# generator.net
KiCad netlist of a schematic drawn in EAGLE
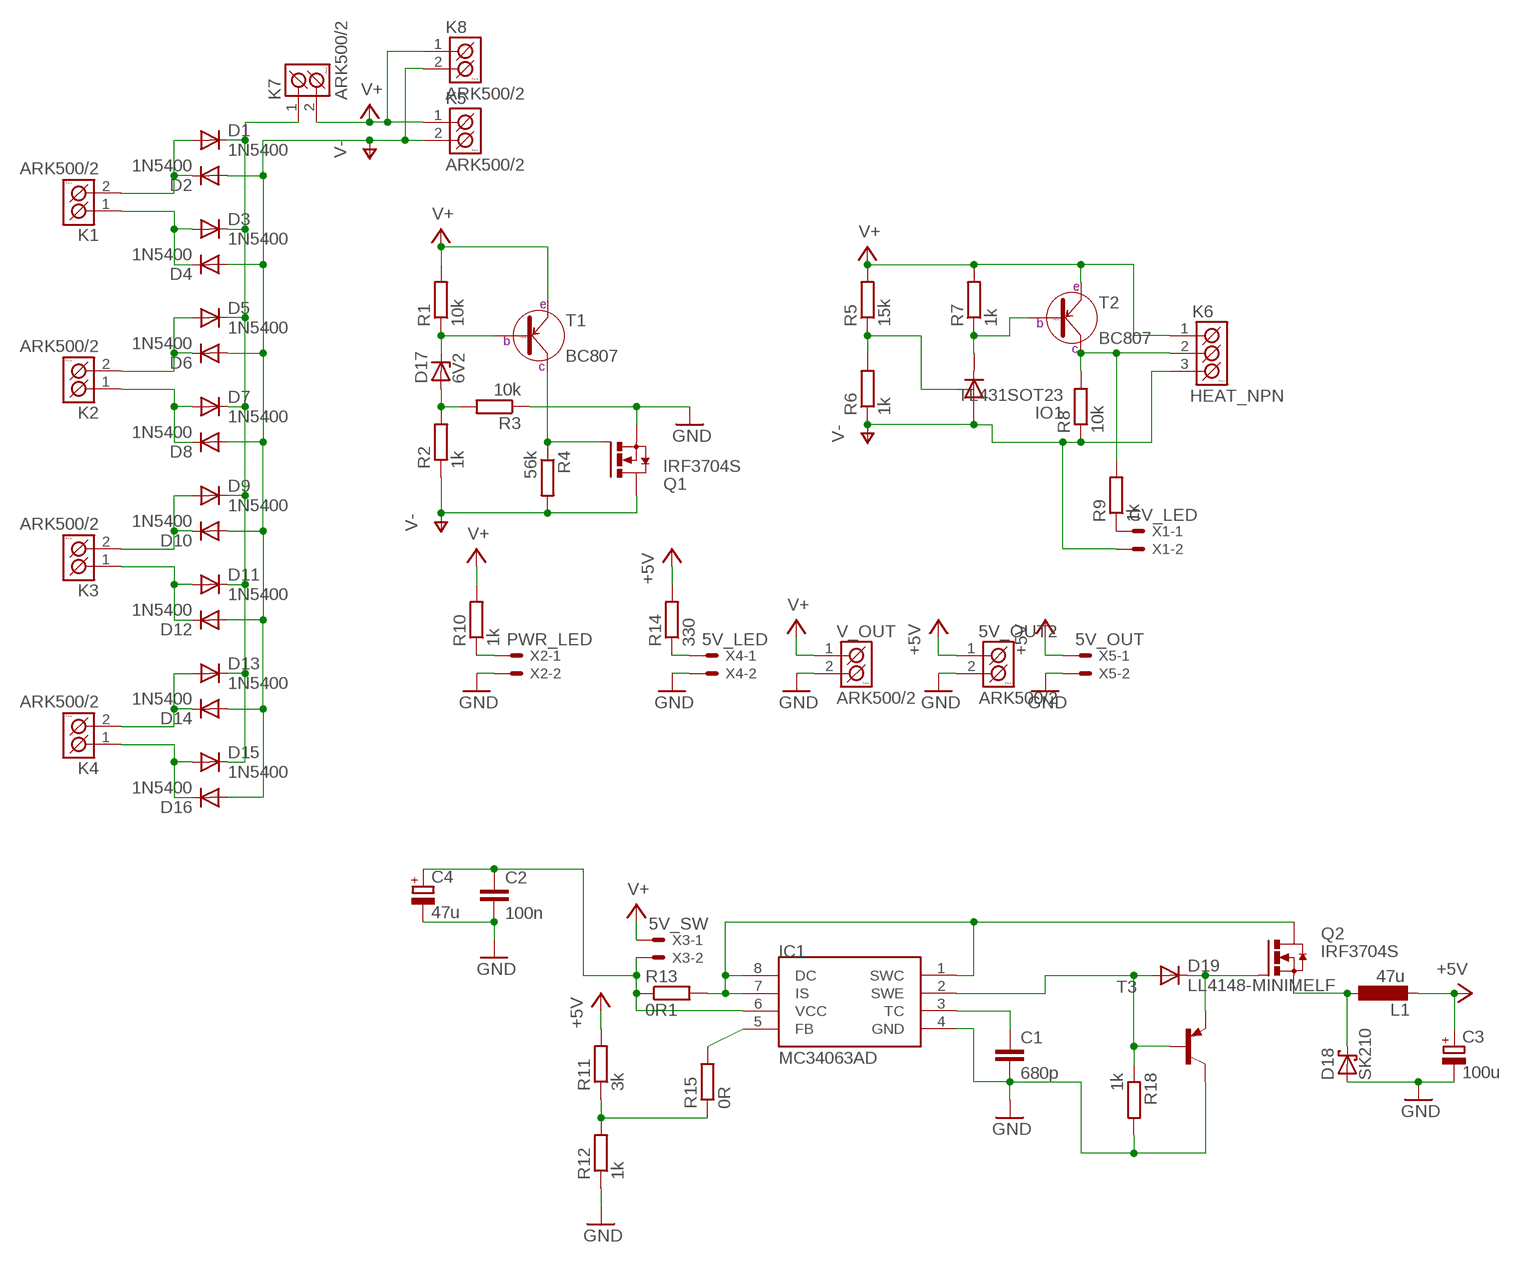
[diagram p0: schematic, sheet 1]

(export (version "E")
  (design (tool "Eeschema 10.0.6"))
  (components
    (comp (ref "5V_OUT2")
      (value "ARK500/2")
      (footprint "eagle-import:ARK500_2")
      (libsource (lib "eagle-import") (part "ARK500/2"))
    )
    (comp (ref "C1")
      (value "680p")
      (footprint "eagle-import:C0805")
      (libsource (lib "eagle-import") (part "C-EUC0805"))
    )
    (comp (ref "C2")
      (value "100n")
      (footprint "eagle-import:C0805")
      (libsource (lib "eagle-import") (part "C-EUC0805"))
    )
    (comp (ref "C3")
      (value "100u")
      (footprint "eagle-import:PANASONIC_D")
      (libsource (lib "eagle-import") (part "CPOL-EUD"))
    )
    (comp (ref "C4")
      (value "47u")
      (footprint "eagle-import:PANASONIC_D")
      (libsource (lib "eagle-import") (part "CPOL-EUD"))
    )
    (comp (ref "D1")
      (value "1N5400")
      (footprint "eagle-import:DO201-15")
      (libsource (lib "eagle-import") (part "1N5400"))
    )
    (comp (ref "D2")
      (value "1N5400")
      (footprint "eagle-import:DO201-15")
      (libsource (lib "eagle-import") (part "1N5400"))
    )
    (comp (ref "D3")
      (value "1N5400")
      (footprint "eagle-import:DO201-15")
      (libsource (lib "eagle-import") (part "1N5400"))
    )
    (comp (ref "D4")
      (value "1N5400")
      (footprint "eagle-import:DO201-15")
      (libsource (lib "eagle-import") (part "1N5400"))
    )
    (comp (ref "D5")
      (value "1N5400")
      (footprint "eagle-import:DO201-15")
      (libsource (lib "eagle-import") (part "1N5400"))
    )
    (comp (ref "D6")
      (value "1N5400")
      (footprint "eagle-import:DO201-15")
      (libsource (lib "eagle-import") (part "1N5400"))
    )
    (comp (ref "D7")
      (value "1N5400")
      (footprint "eagle-import:DO201-15")
      (libsource (lib "eagle-import") (part "1N5400"))
    )
    (comp (ref "D8")
      (value "1N5400")
      (footprint "eagle-import:DO201-15")
      (libsource (lib "eagle-import") (part "1N5400"))
    )
    (comp (ref "D9")
      (value "1N5400")
      (footprint "eagle-import:DO201-15")
      (libsource (lib "eagle-import") (part "1N5400"))
    )
    (comp (ref "D10")
      (value "1N5400")
      (footprint "eagle-import:DO201-15")
      (libsource (lib "eagle-import") (part "1N5400"))
    )
    (comp (ref "D11")
      (value "1N5400")
      (footprint "eagle-import:DO201-15")
      (libsource (lib "eagle-import") (part "1N5400"))
    )
    (comp (ref "D12")
      (value "1N5400")
      (footprint "eagle-import:DO201-15")
      (libsource (lib "eagle-import") (part "1N5400"))
    )
    (comp (ref "D13")
      (value "1N5400")
      (footprint "eagle-import:DO201-15")
      (libsource (lib "eagle-import") (part "1N5400"))
    )
    (comp (ref "D14")
      (value "1N5400")
      (footprint "eagle-import:DO201-15")
      (libsource (lib "eagle-import") (part "1N5400"))
    )
    (comp (ref "D15")
      (value "1N5400")
      (footprint "eagle-import:DO201-15")
      (libsource (lib "eagle-import") (part "1N5400"))
    )
    (comp (ref "D16")
      (value "1N5400")
      (footprint "eagle-import:DO201-15")
      (libsource (lib "eagle-import") (part "1N5400"))
    )
    (comp (ref "D17")
      (value "6V2")
      (footprint "eagle-import:SOD80C")
      (libsource (lib "eagle-import") (part "ZENER-DIODESOD80C"))
    )
    (comp (ref "D18")
      (value "SK210")
      (footprint "eagle-import:SMB")
      (libsource (lib "eagle-import") (part "SCHOTTKY-DIODESMD"))
    )
    (comp (ref "D19")
      (value "LL4148-MINIMELF")
      (footprint "eagle-import:SOD80C")
      (libsource (lib "eagle-import") (part "PMLL41SOD80C"))
    )
    (comp (ref "IC1")
      (value "MC34063AD")
      (footprint "eagle-import:SOIC8")
      (libsource (lib "eagle-import") (part "MC34063AD"))
    )
    (comp (ref "IO1")
      (value "TL431SOT23")
      (footprint "eagle-import:SOT23")
      (fields (field (name "MPN") "TL431BFDT"))
      (libsource (lib "eagle-import") (part "TL431SOT23"))
    )
    (comp (ref "K1")
      (value "ARK500/2")
      (footprint "eagle-import:ARK500_2")
      (libsource (lib "eagle-import") (part "ARK500/2"))
    )
    (comp (ref "K2")
      (value "ARK500/2")
      (footprint "eagle-import:ARK500_2")
      (libsource (lib "eagle-import") (part "ARK500/2"))
    )
    (comp (ref "K3")
      (value "ARK500/2")
      (footprint "eagle-import:ARK500_2")
      (libsource (lib "eagle-import") (part "ARK500/2"))
    )
    (comp (ref "K4")
      (value "ARK500/2")
      (footprint "eagle-import:ARK500_2")
      (libsource (lib "eagle-import") (part "ARK500/2"))
    )
    (comp (ref "K5")
      (value "ARK500/2")
      (footprint "eagle-import:ARK500_2")
      (libsource (lib "eagle-import") (part "ARK500/2"))
    )
    (comp (ref "K6")
      (value "HEAT_NPN")
      (footprint "eagle-import:ARK500_3")
      (libsource (lib "eagle-import") (part "ARK500/3"))
    )
    (comp (ref "K7")
      (value "ARK500/2")
      (footprint "eagle-import:ARK500_2")
      (libsource (lib "eagle-import") (part "ARK500/2"))
    )
    (comp (ref "K8")
      (value "ARK500/2")
      (footprint "eagle-import:ARK500_2")
      (libsource (lib "eagle-import") (part "ARK500/2"))
    )
    (comp (ref "L1")
      (value "47u")
      (footprint "eagle-import:TJ3-U1")
      (libsource (lib "eagle-import") (part "L-EUTJ3-U1"))
    )
    (comp (ref "Q1")
      (value "IRF3704S")
      (footprint "eagle-import:D2PACK")
      (libsource (lib "eagle-import") (part "IRF3704S"))
    )
    (comp (ref "Q2")
      (value "IRF3704S")
      (footprint "eagle-import:D2PACK")
      (libsource (lib "eagle-import") (part "IRF3704S"))
    )
    (comp (ref "R1")
      (value "10k")
      (footprint "eagle-import:R0805")
      (libsource (lib "eagle-import") (part "R-EU_R0805"))
    )
    (comp (ref "R2")
      (value "1k")
      (footprint "eagle-import:R0805")
      (libsource (lib "eagle-import") (part "R-EU_R0805"))
    )
    (comp (ref "R3")
      (value "10k")
      (footprint "eagle-import:R0805")
      (libsource (lib "eagle-import") (part "R-EU_R0805"))
    )
    (comp (ref "R4")
      (value "56k")
      (footprint "eagle-import:R0805")
      (libsource (lib "eagle-import") (part "R-EU_R0805"))
    )
    (comp (ref "R5")
      (value "15k")
      (footprint "eagle-import:R0805")
      (libsource (lib "eagle-import") (part "R-EU_R0805"))
    )
    (comp (ref "R6")
      (value "1k")
      (footprint "eagle-import:R0805")
      (libsource (lib "eagle-import") (part "R-EU_R0805"))
    )
    (comp (ref "R7")
      (value "1k")
      (footprint "eagle-import:R0805")
      (libsource (lib "eagle-import") (part "R-EU_R0805"))
    )
    (comp (ref "R8")
      (value "10k")
      (footprint "eagle-import:R0805")
      (libsource (lib "eagle-import") (part "R-EU_R0805"))
    )
    (comp (ref "R9")
      (value "1k")
      (footprint "eagle-import:R0805")
      (libsource (lib "eagle-import") (part "R-EU_R0805"))
    )
    (comp (ref "R10")
      (value "1k")
      (footprint "eagle-import:R0805")
      (libsource (lib "eagle-import") (part "R-EU_R0805"))
    )
    (comp (ref "R11")
      (value "3k")
      (footprint "eagle-import:R0805")
      (libsource (lib "eagle-import") (part "R-EU_R0805"))
    )
    (comp (ref "R12")
      (value "1k")
      (footprint "eagle-import:R0805")
      (libsource (lib "eagle-import") (part "R-EU_R0805"))
    )
    (comp (ref "R13")
      (value "0R1")
      (footprint "eagle-import:R0805")
      (libsource (lib "eagle-import") (part "R-EU_R0805"))
    )
    (comp (ref "R14")
      (value "330")
      (footprint "eagle-import:R0805")
      (libsource (lib "eagle-import") (part "R-EU_R0805"))
    )
    (comp (ref "R15")
      (value "0R")
      (footprint "eagle-import:R1206")
      (libsource (lib "eagle-import") (part "R-EU_R1206"))
    )
    (comp (ref "R18")
      (value "1k")
      (footprint "eagle-import:R0805")
      (libsource (lib "eagle-import") (part "resistor_R-EU_R0805"))
    )
    (comp (ref "T1")
      (value "BC807")
      (footprint "eagle-import:SOT-23")
      (libsource (lib "eagle-import") (part "BC807"))
    )
    (comp (ref "T2")
      (value "BC807")
      (footprint "eagle-import:SOT-23")
      (libsource (lib "eagle-import") (part "BC807"))
    )
    (comp (ref "T3")
      (value "BC807-16-PNP-SOT23-BEC")
      (footprint "eagle-import:SOT23-BEC")
      (libsource (lib "eagle-import") (part "-PNP-SOT23-BECBC807-16"))
    )
    (comp (ref "V_OUT")
      (value "ARK500/2")
      (footprint "eagle-import:ARK500_2")
      (libsource (lib "eagle-import") (part "ARK500/2"))
    )
    (comp (ref "X1")
      (value "CV_LED")
      (footprint "eagle-import:22-23-2021")
      (fields (field (name "MF") "MOLEX") (field (name "MPN") "22-23-2021"))
      (libsource (lib "eagle-import") (part "22-23-2021"))
    )
    (comp (ref "X2")
      (value "PWR_LED")
      (footprint "eagle-import:22-23-2021")
      (fields (field (name "MF") "MOLEX") (field (name "MPN") "22-23-2021"))
      (libsource (lib "eagle-import") (part "22-23-2021"))
    )
    (comp (ref "X3")
      (value "5V_SW")
      (footprint "eagle-import:22-23-2021")
      (fields (field (name "MF") "MOLEX") (field (name "MPN") "22-23-2021"))
      (libsource (lib "eagle-import") (part "22-23-2021"))
    )
    (comp (ref "X4")
      (value "5V_LED")
      (footprint "eagle-import:22-23-2021")
      (fields (field (name "MF") "MOLEX") (field (name "MPN") "22-23-2021"))
      (libsource (lib "eagle-import") (part "22-23-2021"))
    )
    (comp (ref "X5")
      (value "5V_OUT")
      (footprint "eagle-import:22-23-2021")
      (fields (field (name "MF") "MOLEX") (field (name "MPN") "22-23-2021"))
      (libsource (lib "eagle-import") (part "22-23-2021"))
    )
  )
  (nets
    (net (code "1") (name "+5V") (class "Default")
      (node (ref "5V_OUT2") (pin "1") (pinfunction "K1_1") (pintype "passive"))
      (node (ref "C3") (pin "+") (pinfunction "+_+") (pintype "passive"))
      (node (ref "L1") (pin "2") (pinfunction "2_2") (pintype "passive"))
      (node (ref "R11") (pin "2") (pinfunction "2_2") (pintype "passive"))
      (node (ref "R14") (pin "2") (pinfunction "2_2") (pintype "passive"))
      (node (ref "X5") (pin "1") (pinfunction "S_1") (pintype "passive"))
    )
    (net (code "2") (name "GND") (class "Default")
      (node (ref "5V_OUT2") (pin "2") (pinfunction "K2_2") (pintype "passive"))
      (node (ref "C1") (pin "2") (pinfunction "2_2") (pintype "passive"))
      (node (ref "C2") (pin "2") (pinfunction "2_2") (pintype "passive"))
      (node (ref "C3") (pin "-") (pinfunction "-_-") (pintype "passive"))
      (node (ref "C4") (pin "-") (pinfunction "-_-") (pintype "passive"))
      (node (ref "D18") (pin "A") (pinfunction "A_A") (pintype "passive"))
      (node (ref "IC1") (pin "4") (pinfunction "GND_4") (pintype "passive"))
      (node (ref "Q1") (pin "3") (pinfunction "S_3") (pintype "passive"))
      (node (ref "R12") (pin "1") (pinfunction "1_1") (pintype "passive"))
      (node (ref "R18") (pin "2") (pinfunction "2_2") (pintype "passive"))
      (node (ref "R3") (pin "1") (pinfunction "1_1") (pintype "passive"))
      (node (ref "T3") (pin "C") (pinfunction "C_C") (pintype "passive"))
      (node (ref "V_OUT") (pin "2") (pinfunction "K2_2") (pintype "passive"))
      (node (ref "X2") (pin "2") (pinfunction "S_2") (pintype "passive"))
      (node (ref "X4") (pin "2") (pinfunction "S_2") (pintype "passive"))
      (node (ref "X5") (pin "2") (pinfunction "S_2") (pintype "passive"))
    )
    (net (code "3") (name "Net-(D17-PadA)") (class "Default")
      (node (ref "D17") (pin "A") (pinfunction "A_A") (pintype "passive"))
      (node (ref "R2") (pin "2") (pinfunction "2_2") (pintype "passive"))
      (node (ref "R3") (pin "2") (pinfunction "2_2") (pintype "passive"))
    )
    (net (code "4") (name "Net-(IC1-DC)") (class "Default")
      (node (ref "IC1") (pin "1") (pinfunction "SWC_1") (pintype "passive"))
      (node (ref "IC1") (pin "7") (pinfunction "IS_7") (pintype "passive"))
      (node (ref "IC1") (pin "8") (pinfunction "DC_8") (pintype "passive"))
      (node (ref "Q2") (pin "2") (pinfunction "D_2") (pintype "passive"))
      (node (ref "R13") (pin "2") (pinfunction "2_2") (pintype "passive"))
    )
    (net (code "5") (name "Net-(IC1-FB)") (class "Default")
      (node (ref "IC1") (pin "5") (pinfunction "FB_5") (pintype "passive"))
      (node (ref "R15") (pin "2") (pinfunction "2_2") (pintype "passive"))
    )
    (net (code "6") (name "Net-(IC1-SWE)") (class "Default")
      (node (ref "D19") (pin "A") (pinfunction "A_A") (pintype "passive"))
      (node (ref "IC1") (pin "2") (pinfunction "SWE_2") (pintype "passive"))
      (node (ref "R18") (pin "1") (pinfunction "1_1") (pintype "passive"))
      (node (ref "T3") (pin "B") (pinfunction "B_B") (pintype "passive"))
    )
    (net (code "7") (name "Net-(IC1-TC)") (class "Default")
      (node (ref "C1") (pin "1") (pinfunction "1_1") (pintype "passive"))
      (node (ref "IC1") (pin "3") (pinfunction "TC_3") (pintype "passive"))
    )
    (net (code "8") (name "Net-(IC1-VCC)") (class "Default")
      (node (ref "C2") (pin "1") (pinfunction "1_1") (pintype "passive"))
      (node (ref "C4") (pin "+") (pinfunction "+_+") (pintype "passive"))
      (node (ref "IC1") (pin "6") (pinfunction "VCC_6") (pintype "passive"))
      (node (ref "R13") (pin "1") (pinfunction "1_1") (pintype "passive"))
      (node (ref "X3") (pin "2") (pinfunction "S_2") (pintype "passive"))
    )
    (net (code "9") (name "Net-(IO1-C)") (class "Default")
      (node (ref "IO1") (pin "1") (pinfunction "C_1") (pintype "bidirectional"))
      (node (ref "R7") (pin "1") (pinfunction "1_1") (pintype "passive"))
      (node (ref "T2") (pin "1") (pinfunction "B_1") (pintype "passive"))
    )
    (net (code "10") (name "Net-(IO1-R)") (class "Default")
      (node (ref "IO1") (pin "2") (pinfunction "R_2") (pintype "bidirectional"))
      (node (ref "R5") (pin "1") (pinfunction "1_1") (pintype "passive"))
      (node (ref "R6") (pin "2") (pinfunction "2_2") (pintype "passive"))
    )
    (net (code "11") (name "Net-(K1-K1)") (class "Default")
      (node (ref "D3") (pin "A") (pinfunction "A_A") (pintype "passive"))
      (node (ref "D4") (pin "C") (pinfunction "C_C") (pintype "passive"))
      (node (ref "K1") (pin "1") (pinfunction "K1_1") (pintype "passive"))
    )
    (net (code "12") (name "Net-(K1-K2)") (class "Default")
      (node (ref "D1") (pin "A") (pinfunction "A_A") (pintype "passive"))
      (node (ref "D2") (pin "C") (pinfunction "C_C") (pintype "passive"))
      (node (ref "K1") (pin "2") (pinfunction "K2_2") (pintype "passive"))
    )
    (net (code "13") (name "Net-(K2-K1)") (class "Default")
      (node (ref "D7") (pin "A") (pinfunction "A_A") (pintype "passive"))
      (node (ref "D8") (pin "C") (pinfunction "C_C") (pintype "passive"))
      (node (ref "K2") (pin "1") (pinfunction "K1_1") (pintype "passive"))
    )
    (net (code "14") (name "Net-(K2-K2)") (class "Default")
      (node (ref "D5") (pin "A") (pinfunction "A_A") (pintype "passive"))
      (node (ref "D6") (pin "C") (pinfunction "C_C") (pintype "passive"))
      (node (ref "K2") (pin "2") (pinfunction "K2_2") (pintype "passive"))
    )
    (net (code "15") (name "Net-(K3-K1)") (class "Default")
      (node (ref "D11") (pin "A") (pinfunction "A_A") (pintype "passive"))
      (node (ref "D12") (pin "C") (pinfunction "C_C") (pintype "passive"))
      (node (ref "K3") (pin "1") (pinfunction "K1_1") (pintype "passive"))
    )
    (net (code "16") (name "Net-(K3-K2)") (class "Default")
      (node (ref "D10") (pin "C") (pinfunction "C_C") (pintype "passive"))
      (node (ref "D9") (pin "A") (pinfunction "A_A") (pintype "passive"))
      (node (ref "K3") (pin "2") (pinfunction "K2_2") (pintype "passive"))
    )
    (net (code "17") (name "Net-(K4-K1)") (class "Default")
      (node (ref "D15") (pin "A") (pinfunction "A_A") (pintype "passive"))
      (node (ref "D16") (pin "C") (pinfunction "C_C") (pintype "passive"))
      (node (ref "K4") (pin "1") (pinfunction "K1_1") (pintype "passive"))
    )
    (net (code "18") (name "Net-(K4-K2)") (class "Default")
      (node (ref "D13") (pin "A") (pinfunction "A_A") (pintype "passive"))
      (node (ref "D14") (pin "C") (pinfunction "C_C") (pintype "passive"))
      (node (ref "K4") (pin "2") (pinfunction "K2_2") (pintype "passive"))
    )
    (net (code "19") (name "Net-(K6-K2)") (class "Default")
      (node (ref "K6") (pin "2") (pinfunction "K2_2") (pintype "passive"))
      (node (ref "R8") (pin "2") (pinfunction "2_2") (pintype "passive"))
      (node (ref "R9") (pin "2") (pinfunction "2_2") (pintype "passive"))
      (node (ref "T2") (pin "3") (pinfunction "C_3") (pintype "passive"))
    )
    (net (code "20") (name "Net-(K7-K1)") (class "Default")
      (node (ref "D1") (pin "C") (pinfunction "C_C") (pintype "passive"))
      (node (ref "D11") (pin "C") (pinfunction "C_C") (pintype "passive"))
      (node (ref "D13") (pin "C") (pinfunction "C_C") (pintype "passive"))
      (node (ref "D15") (pin "C") (pinfunction "C_C") (pintype "passive"))
      (node (ref "D3") (pin "C") (pinfunction "C_C") (pintype "passive"))
      (node (ref "D5") (pin "C") (pinfunction "C_C") (pintype "passive"))
      (node (ref "D7") (pin "C") (pinfunction "C_C") (pintype "passive"))
      (node (ref "D9") (pin "C") (pinfunction "C_C") (pintype "passive"))
      (node (ref "K7") (pin "1") (pinfunction "K1_1") (pintype "passive"))
    )
    (net (code "21") (name "Net-(Q1-G)") (class "Default")
      (node (ref "Q1") (pin "1") (pinfunction "G_1") (pintype "passive"))
      (node (ref "R4") (pin "1") (pinfunction "1_1") (pintype "passive"))
      (node (ref "T1") (pin "3") (pinfunction "C_3") (pintype "passive"))
    )
    (net (code "22") (name "Net-(Q2-G)") (class "Default")
      (node (ref "D19") (pin "C") (pinfunction "C_C") (pintype "passive"))
      (node (ref "Q2") (pin "1") (pinfunction "G_1") (pintype "passive"))
      (node (ref "T3") (pin "E") (pinfunction "E_E") (pintype "passive"))
    )
    (net (code "23") (name "Net-(Q2-S)") (class "Default")
      (node (ref "D18") (pin "C") (pinfunction "C_C") (pintype "passive"))
      (node (ref "L1") (pin "1") (pinfunction "1_1") (pintype "passive"))
      (node (ref "Q2") (pin "3") (pinfunction "S_3") (pintype "passive"))
    )
    (net (code "24") (name "Net-(R11-Pad1)") (class "Default")
      (node (ref "R11") (pin "1") (pinfunction "1_1") (pintype "passive"))
      (node (ref "R12") (pin "2") (pinfunction "2_2") (pintype "passive"))
      (node (ref "R15") (pin "1") (pinfunction "1_1") (pintype "passive"))
    )
    (net (code "25") (name "Net-(T1-B)") (class "Default")
      (node (ref "D17") (pin "C") (pinfunction "C_C") (pintype "passive"))
      (node (ref "R1") (pin "1") (pinfunction "1_1") (pintype "passive"))
      (node (ref "T1") (pin "1") (pinfunction "B_1") (pintype "passive"))
    )
    (net (code "26") (name "Net-(X1A-S)") (class "Default")
      (node (ref "R9") (pin "1") (pinfunction "1_1") (pintype "passive"))
      (node (ref "X1") (pin "1") (pinfunction "S_1") (pintype "passive"))
    )
    (net (code "27") (name "Net-(X2A-S)") (class "Default")
      (node (ref "R10") (pin "1") (pinfunction "1_1") (pintype "passive"))
      (node (ref "X2") (pin "1") (pinfunction "S_1") (pintype "passive"))
    )
    (net (code "28") (name "Net-(X4A-S)") (class "Default")
      (node (ref "R14") (pin "1") (pinfunction "1_1") (pintype "passive"))
      (node (ref "X4") (pin "1") (pinfunction "S_1") (pintype "passive"))
    )
    (net (code "29") (name "V+") (class "Default")
      (node (ref "K5") (pin "1") (pinfunction "K1_1") (pintype "passive"))
      (node (ref "K6") (pin "1") (pinfunction "K1_1") (pintype "passive"))
      (node (ref "K7") (pin "2") (pinfunction "K2_2") (pintype "passive"))
      (node (ref "K8") (pin "1") (pinfunction "K1_1") (pintype "passive"))
      (node (ref "R1") (pin "2") (pinfunction "2_2") (pintype "passive"))
      (node (ref "R10") (pin "2") (pinfunction "2_2") (pintype "passive"))
      (node (ref "R5") (pin "2") (pinfunction "2_2") (pintype "passive"))
      (node (ref "R7") (pin "2") (pinfunction "2_2") (pintype "passive"))
      (node (ref "T1") (pin "2") (pinfunction "E_2") (pintype "passive"))
      (node (ref "T2") (pin "2") (pinfunction "E_2") (pintype "passive"))
      (node (ref "V_OUT") (pin "1") (pinfunction "K1_1") (pintype "passive"))
      (node (ref "X3") (pin "1") (pinfunction "S_1") (pintype "passive"))
    )
    (net (code "30") (name "V-") (class "Default")
      (node (ref "D10") (pin "A") (pinfunction "A_A") (pintype "passive"))
      (node (ref "D12") (pin "A") (pinfunction "A_A") (pintype "passive"))
      (node (ref "D14") (pin "A") (pinfunction "A_A") (pintype "passive"))
      (node (ref "D16") (pin "A") (pinfunction "A_A") (pintype "passive"))
      (node (ref "D2") (pin "A") (pinfunction "A_A") (pintype "passive"))
      (node (ref "D4") (pin "A") (pinfunction "A_A") (pintype "passive"))
      (node (ref "D6") (pin "A") (pinfunction "A_A") (pintype "passive"))
      (node (ref "D8") (pin "A") (pinfunction "A_A") (pintype "passive"))
      (node (ref "IO1") (pin "3") (pinfunction "A_3") (pintype "bidirectional"))
      (node (ref "K5") (pin "2") (pinfunction "K2_2") (pintype "passive"))
      (node (ref "K6") (pin "3") (pinfunction "K3_3") (pintype "passive"))
      (node (ref "K8") (pin "2") (pinfunction "K2_2") (pintype "passive"))
      (node (ref "Q1") (pin "2") (pinfunction "D_2") (pintype "passive"))
      (node (ref "R2") (pin "1") (pinfunction "1_1") (pintype "passive"))
      (node (ref "R4") (pin "2") (pinfunction "2_2") (pintype "passive"))
      (node (ref "R6") (pin "1") (pinfunction "1_1") (pintype "passive"))
      (node (ref "R8") (pin "1") (pinfunction "1_1") (pintype "passive"))
      (node (ref "X1") (pin "2") (pinfunction "S_2") (pintype "passive"))
    )
  )
)
